# BMS_LOST_V2.net
KiCad netlist of a schematic drawn in Altium Designer
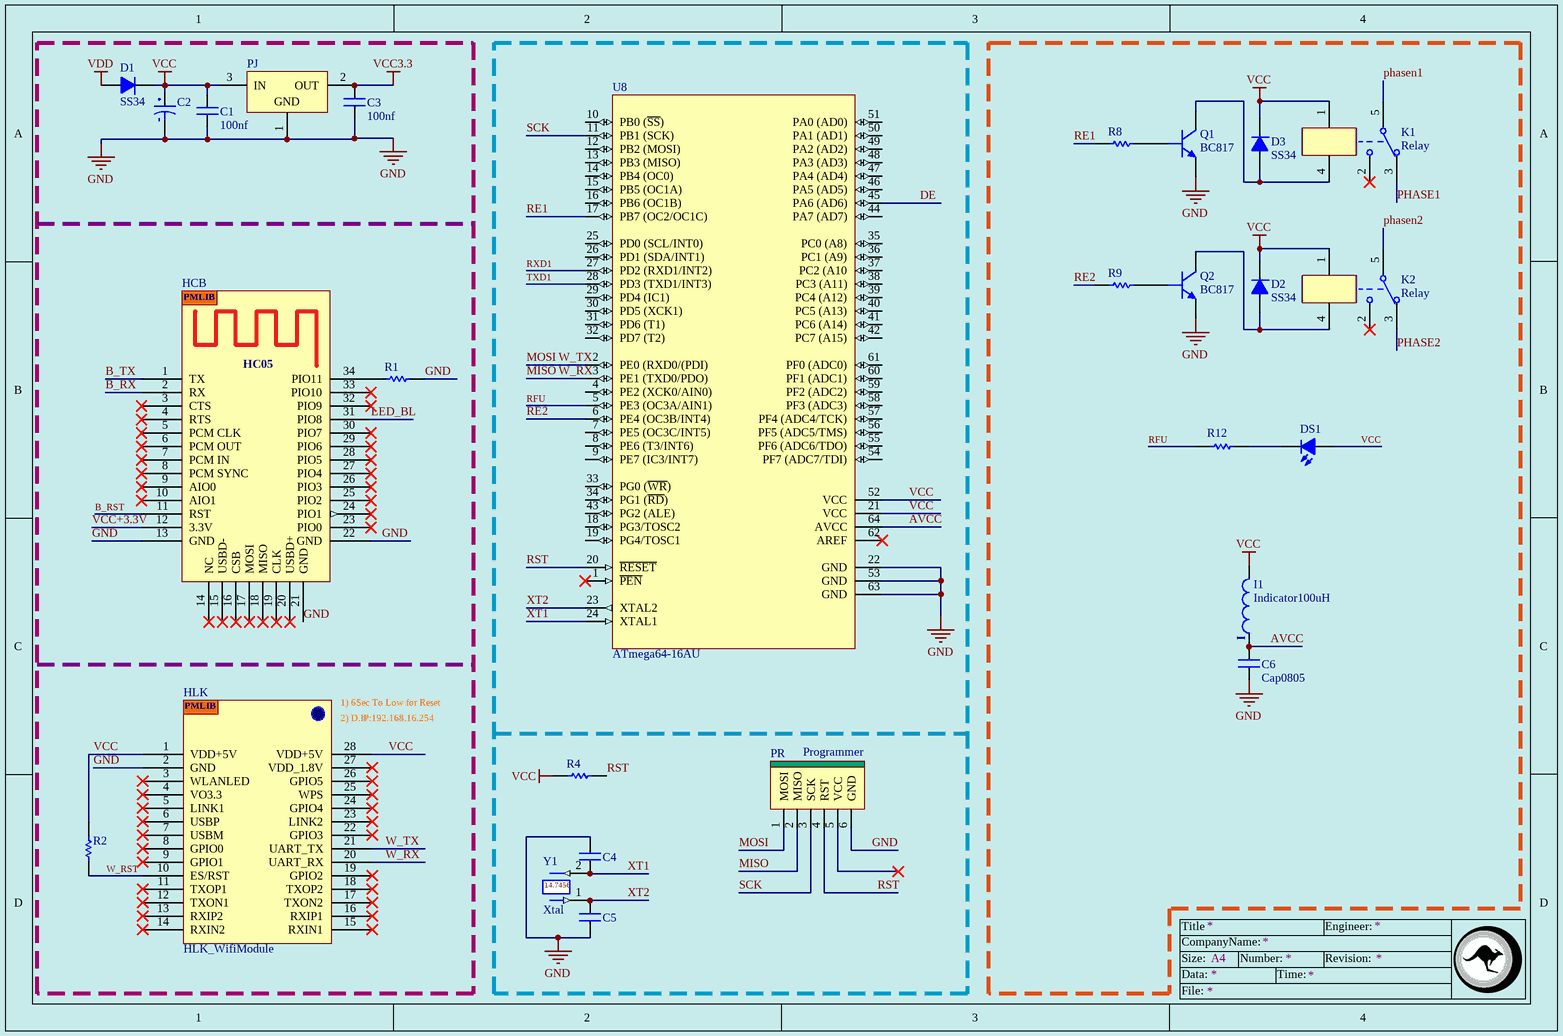
[diagram p0: BMS_LOST_V2.SchDoc]

(export (version "E")
  (design (tool "Eeschema 10.0.6"))
  (components
    (comp (ref "C1")
      (value "100nf")
      (footprint "Cap0805")
      (description "surface mount capacitor (size 805)")
      (libsource (lib "PMLIB") (part "Cap0805"))
    )
    (comp (ref "C2") (value "Cap_4mm") (footprint "2220") (libsource (lib "PMLIB") (part "Cap_Pola")))
    (comp (ref "C3")
      (value "100nf")
      (footprint "Cap0805")
      (description "surface mount capacitor (size 805)")
      (libsource (lib "PMLIB") (part "Cap0805"))
    )
    (comp (ref "C4")
      (value "CAP 805")
      (footprint "Cap0805")
      (description "surface mount capacitor (size 805)")
      (libsource (lib "PMLIB") (part "Cap0805"))
    )
    (comp (ref "C5")
      (value "CAP 805")
      (footprint "Cap0805")
      (description "surface mount capacitor (size 805)")
      (libsource (lib "PMLIB") (part "Cap0805"))
    )
    (comp (ref "C6")
      (value "Cap0805")
      (footprint "Cap0805")
      (description "surface mount capacitor (size 805)")
      (libsource (lib "PMLIB") (part "Cap0805"))
    )
    (comp (ref "D1") (value "SS34") (footprint "Diod-1A-SMD") (libsource (lib "PMLIB") (part "Diode")))
    (comp (ref "D2") (value "SS34") (footprint "Diod-1A-SMD") (libsource (lib "PMLIB") (part "Diode")))
    (comp (ref "D3") (value "SS34") (footprint "Diod-1A-SMD") (libsource (lib "PMLIB") (part "Diode")))
    (comp (ref "DS1") (value "LED1") (footprint "LED3MM") (libsource (lib "PMLIB") (part "LED1")))
    (comp (ref "HC")
      (value "HC05_Bluetooth")
      (footprint "HC05_Bluetooth")
      (libsource (lib "PMLIB") (part "HC05_Bluetooth"))
    )
    (comp (ref "HLK")
      (value "HLK_WifiModule")
      (footprint "HLK")
      (libsource (lib "PMLIB") (part "HLK_WifiModule"))
    )
    (comp (ref "I1")
      (value "Indicator100uH")
      (footprint "Indicator0805")
      (libsource (lib "PMLIB") (part "Indicator100uH"))
    )
    (comp (ref "K1")
      (value "Relay")
      (footprint "RelayMilionMiniS-Z")
      (libsource (lib "PMLIB") (part "RelayMilon"))
    )
    (comp (ref "K2")
      (value "Relay")
      (footprint "RelayMilionMiniS-Z")
      (libsource (lib "PMLIB") (part "RelayMilon"))
    )
    (comp (ref "PJ")
      (value "PJ1117_3.3V")
      (footprint "PJ1117s")
      (libsource (lib "PMLIB") (part "PJ1117_3.3V"))
    )
    (comp (ref "PR")
      (value "Programmer")
      (footprint "Programmer")
      (libsource (lib "PMLIB") (part "Programmer"))
    )
    (comp (ref "Q1") (value "BC817") (footprint "SOT23") (libsource (lib "PMLIB") (part "Transistor NPN")))
    (comp (ref "Q2") (value "BC817") (footprint "SOT23") (libsource (lib "PMLIB") (part "Transistor NPN")))
    (comp (ref "R1") (value "Res 0805") (footprint "R0805") (libsource (lib "PMLIB") (part "Res 0805")))
    (comp (ref "R2") (value "Res 0805") (footprint "R0805") (libsource (lib "PMLIB") (part "Res 0805")))
    (comp (ref "R4") (value "Res 0805") (footprint "R0805") (libsource (lib "PMLIB") (part "Res 0805")))
    (comp (ref "R8") (value "Res 0805") (footprint "R0805") (libsource (lib "PMLIB") (part "Res 0805")))
    (comp (ref "R9") (value "Res 0805") (footprint "R0805") (libsource (lib "PMLIB") (part "Res 0805")))
    (comp (ref "R12") (value "330") (footprint "R0805") (libsource (lib "PMLIB") (part "Res 0805")))
    (comp (ref "U8")
      (value "ATmega64-16AU")
      (footprint "64A_L")
      (libsource (lib "Atmel Microcontroller megaAVR") (part "ATmega64-16AU"))
    )
    (comp (ref "Y1") (value "Xtal") (footprint "CrystallB") (libsource (lib "PMLIB") (part "Crystal")))
  )
  (nets
    (net (code "1") (name "/AVCC") (class "Default")
      (node (ref "C6") (pin "2") (pinfunction "2_2") (pintype "passive"))
      (node (ref "I1") (pin "1") (pinfunction "1_1") (pintype "passive"))
      (node (ref "U8") (pin "64") (pinfunction "AVCC_64") (pintype "power_in"))
    )
    (net (code "2") (name "/B_RST") (class "Default")
      (node (ref "HC") (pin "11") (pinfunction "RST_11") (pintype "passive"))
    )
    (net (code "3") (name "/B_RX") (class "Default")
      (node (ref "HC") (pin "2") (pinfunction "RX_2") (pintype "passive"))
    )
    (net (code "4") (name "/B_TX") (class "Default")
      (node (ref "HC") (pin "1") (pinfunction "TX_1") (pintype "passive"))
    )
    (net (code "5") (name "/DE") (class "Default")
      (node (ref "U8") (pin "45") (pinfunction "PA6_(AD6)_45") (pintype "bidirectional"))
    )
    (net (code "6") (name "/LED_BL") (class "Default")
      (node (ref "HC") (pin "31") (pinfunction "PIO8_31") (pintype "passive"))
    )
    (net (code "7") (name "/MISO") (class "Default")
      (node (ref "HLK") (pin "20") (pinfunction "UART_RX_20") (pintype "passive"))
      (node (ref "PR") (pin "2") (pinfunction "MISO_2") (pintype "passive"))
      (node (ref "U8") (pin "3") (pinfunction "PE1_(TXD0/PDO)_3") (pintype "bidirectional"))
    )
    (net (code "8") (name "/MOSI") (class "Default")
      (node (ref "HLK") (pin "21") (pinfunction "UART_TX_21") (pintype "passive"))
      (node (ref "PR") (pin "1") (pinfunction "MOSI_1") (pintype "passive"))
      (node (ref "U8") (pin "2") (pinfunction "PE0_(RXD0/(PDI)_2") (pintype "bidirectional"))
    )
    (net (code "9") (name "/PHASE1") (class "Default")
      (node (ref "K1") (pin "3") (pinfunction "3_3") (pintype "passive"))
    )
    (net (code "10") (name "/PHASE2") (class "Default")
      (node (ref "K2") (pin "3") (pinfunction "3_3") (pintype "passive"))
    )
    (net (code "11") (name "/RE1") (class "Default")
      (node (ref "R8") (pin "2") (pinfunction "2_2") (pintype "passive"))
      (node (ref "U8") (pin "17") (pinfunction "PB7_(OC2/OC1C)_17") (pintype "bidirectional"))
    )
    (net (code "12") (name "/RE2") (class "Default")
      (node (ref "R9") (pin "2") (pinfunction "2_2") (pintype "passive"))
      (node (ref "U8") (pin "6") (pinfunction "PE4_(OC3B/INT4)_6") (pintype "bidirectional"))
    )
    (net (code "13") (name "/RFU") (class "Default")
      (node (ref "R12") (pin "2") (pinfunction "2_2") (pintype "passive"))
      (node (ref "U8") (pin "5") (pinfunction "PE3_(OC3A/AIN1)_5") (pintype "bidirectional"))
    )
    (net (code "14") (name "/RST") (class "Default")
      (node (ref "PR") (pin "4") (pinfunction "RST_4") (pintype "passive"))
      (node (ref "R4") (pin "1") (pinfunction "1_1") (pintype "passive"))
      (node (ref "U8") (pin "20") (pinfunction "~{RESET}_20") (pintype "input"))
    )
    (net (code "15") (name "/RXD1") (class "Default")
      (node (ref "U8") (pin "27") (pinfunction "PD2_(RXD1/INT2)_27") (pintype "bidirectional"))
    )
    (net (code "16") (name "/SCK") (class "Default")
      (node (ref "PR") (pin "3") (pinfunction "SCK_3") (pintype "passive"))
      (node (ref "U8") (pin "11") (pinfunction "PB1_(SCK)_11") (pintype "bidirectional"))
    )
    (net (code "17") (name "/TXD1") (class "Default")
      (node (ref "U8") (pin "28") (pinfunction "PD3_(TXD1/INT3)_28") (pintype "bidirectional"))
    )
    (net (code "18") (name "/VCC+3.3V") (class "Default")
      (node (ref "HC") (pin "12") (pinfunction "3.3V_12") (pintype "passive"))
    )
    (net (code "19") (name "/W_RST") (class "Default")
      (node (ref "HLK") (pin "10") (pinfunction "ES/RST_10") (pintype "passive"))
      (node (ref "R2") (pin "2") (pinfunction "2_2") (pintype "passive"))
    )
    (net (code "20") (name "/XT1") (class "Default")
      (node (ref "C4") (pin "1") (pinfunction "1_1") (pintype "passive"))
      (node (ref "U8") (pin "24") (pinfunction "XTAL1_24") (pintype "input"))
      (node (ref "Y1") (pin "2") (pinfunction "2_2") (pintype "input"))
    )
    (net (code "21") (name "/XT2") (class "Default")
      (node (ref "C5") (pin "1") (pinfunction "1_1") (pintype "passive"))
      (node (ref "U8") (pin "23") (pinfunction "XTAL2_23") (pintype "output"))
      (node (ref "Y1") (pin "1") (pinfunction "1_1") (pintype "output"))
    )
    (net (code "22") (name "/phasen1") (class "Default")
      (node (ref "K1") (pin "5") (pinfunction "5_5") (pintype "passive"))
    )
    (net (code "23") (name "/phasen2") (class "Default")
      (node (ref "K2") (pin "5") (pinfunction "5_5") (pintype "passive"))
    )
    (net (code "24") (name "GND") (class "Default")
      (node (ref "C1") (pin "2") (pinfunction "2_2") (pintype "passive"))
      (node (ref "C2") (pin "1") (pinfunction "1_1") (pintype "passive"))
      (node (ref "C3") (pin "2") (pinfunction "2_2") (pintype "passive"))
      (node (ref "C4") (pin "2") (pinfunction "2_2") (pintype "passive"))
      (node (ref "C5") (pin "2") (pinfunction "2_2") (pintype "passive"))
      (node (ref "C6") (pin "1") (pinfunction "1_1") (pintype "passive"))
      (node (ref "HC") (pin "13") (pinfunction "GND_13") (pintype "power_in"))
      (node (ref "HC") (pin "21") (pinfunction "GND_21") (pintype "passive"))
      (node (ref "HC") (pin "22") (pinfunction "GND_22") (pintype "passive"))
      (node (ref "HLK") (pin "2") (pinfunction "GND_2") (pintype "passive"))
      (node (ref "PJ") (pin "1") (pinfunction "GND_1") (pintype "power_in"))
      (node (ref "PR") (pin "6") (pinfunction "GND_6") (pintype "passive"))
      (node (ref "Q1") (pin "2") (pinfunction "E_2") (pintype "passive"))
      (node (ref "Q2") (pin "2") (pinfunction "E_2") (pintype "passive"))
      (node (ref "R1") (pin "1") (pinfunction "1_1") (pintype "passive"))
      (node (ref "U8") (pin "22") (pinfunction "GND_22") (pintype "power_in"))
      (node (ref "U8") (pin "53") (pinfunction "GND_53") (pintype "power_in"))
      (node (ref "U8") (pin "63") (pinfunction "GND_63") (pintype "power_in"))
    )
    (net (code "25") (name "Net-(DS1-PadK)") (class "Default")
      (node (ref "DS1") (pin "K") (pinfunction "K_K") (pintype "passive"))
      (node (ref "R12") (pin "1") (pinfunction "1_1") (pintype "passive"))
    )
    (net (code "26") (name "Net-(HCB-PIO11)") (class "Default")
      (node (ref "HC") (pin "34") (pinfunction "PIO11_34") (pintype "passive"))
      (node (ref "R1") (pin "2") (pinfunction "2_2") (pintype "passive"))
    )
    (net (code "27") (name "Net-(Q1-B)") (class "Default")
      (node (ref "Q1") (pin "1") (pinfunction "B_1") (pintype "passive"))
      (node (ref "R8") (pin "1") (pinfunction "1_1") (pintype "passive"))
    )
    (net (code "28") (name "Net-(Q1-C)") (class "Default")
      (node (ref "D3") (pin "A") (pinfunction "A_A") (pintype "passive"))
      (node (ref "K1") (pin "4") (pinfunction "4_4") (pintype "passive"))
      (node (ref "Q1") (pin "3") (pinfunction "C_3") (pintype "passive"))
    )
    (net (code "29") (name "Net-(Q2-B)") (class "Default")
      (node (ref "Q2") (pin "1") (pinfunction "B_1") (pintype "passive"))
      (node (ref "R9") (pin "1") (pinfunction "1_1") (pintype "passive"))
    )
    (net (code "30") (name "Net-(Q2-C)") (class "Default")
      (node (ref "D2") (pin "A") (pinfunction "A_A") (pintype "passive"))
      (node (ref "K2") (pin "4") (pinfunction "4_4") (pintype "passive"))
      (node (ref "Q2") (pin "3") (pinfunction "C_3") (pintype "passive"))
    )
    (net (code "31") (name "VCC") (class "Default")
      (node (ref "C1") (pin "1") (pinfunction "1_1") (pintype "passive"))
      (node (ref "C2") (pin "2") (pinfunction "2_2") (pintype "passive"))
      (node (ref "D1") (pin "K") (pinfunction "K_K") (pintype "passive"))
      (node (ref "D2") (pin "K") (pinfunction "K_K") (pintype "passive"))
      (node (ref "D3") (pin "K") (pinfunction "K_K") (pintype "passive"))
      (node (ref "DS1") (pin "A") (pinfunction "A_A") (pintype "passive"))
      (node (ref "HLK") (pin "1") (pinfunction "VDD+5V_1") (pintype "passive"))
      (node (ref "HLK") (pin "28") (pinfunction "VDD+5V_28") (pintype "passive"))
      (node (ref "I1") (pin "2") (pinfunction "2_2") (pintype "passive"))
      (node (ref "K1") (pin "1") (pinfunction "1_1") (pintype "passive"))
      (node (ref "K2") (pin "1") (pinfunction "1_1") (pintype "passive"))
      (node (ref "PJ") (pin "3") (pinfunction "IN_3") (pintype "power_in"))
      (node (ref "R2") (pin "1") (pinfunction "1_1") (pintype "passive"))
      (node (ref "R4") (pin "2") (pinfunction "2_2") (pintype "passive"))
      (node (ref "U8") (pin "21") (pinfunction "VCC_21") (pintype "power_in"))
      (node (ref "U8") (pin "52") (pinfunction "VCC_52") (pintype "power_in"))
    )
    (net (code "32") (name "VCC3.3") (class "Default")
      (node (ref "C3") (pin "1") (pinfunction "1_1") (pintype "passive"))
      (node (ref "PJ") (pin "2") (pinfunction "OUT_2") (pintype "power_in"))
    )
    (net (code "33") (name "VDD") (class "Default")
      (node (ref "D1") (pin "A") (pinfunction "A_A") (pintype "passive"))
    )
    (net (code "34") (name "unconnected-(HCB-AIO0-Pad9)") (class "Default")
      (node (ref "HC") (pin "9") (pinfunction "AIO0_9") (pintype "passive+no_connect"))
    )
    (net (code "35") (name "unconnected-(HCB-AIO1-Pad10)") (class "Default")
      (node (ref "HC") (pin "10") (pinfunction "AIO1_10") (pintype "passive+no_connect"))
    )
    (net (code "36") (name "unconnected-(HCB-CLK-Pad19)") (class "Default")
      (node (ref "HC") (pin "19") (pinfunction "CLK_19") (pintype "passive+no_connect"))
    )
    (net (code "37") (name "unconnected-(HCB-CSB-Pad16)") (class "Default")
      (node (ref "HC") (pin "16") (pinfunction "CSB_16") (pintype "passive+no_connect"))
    )
    (net (code "38") (name "unconnected-(HCB-CTS-Pad3)") (class "Default")
      (node (ref "HC") (pin "3") (pinfunction "CTS_3") (pintype "passive+no_connect"))
    )
    (net (code "39") (name "unconnected-(HCB-MISO-Pad18)") (class "Default")
      (node (ref "HC") (pin "18") (pinfunction "MISO_18") (pintype "passive+no_connect"))
    )
    (net (code "40") (name "unconnected-(HCB-MOSI-Pad17)") (class "Default")
      (node (ref "HC") (pin "17") (pinfunction "MOSI_17") (pintype "passive+no_connect"))
    )
    (net (code "41") (name "unconnected-(HCB-NC-Pad14)") (class "Default")
      (node (ref "HC") (pin "14") (pinfunction "NC_14") (pintype "passive+no_connect"))
    )
    (net (code "42") (name "unconnected-(HCB-PCM_CLK-Pad5)") (class "Default")
      (node (ref "HC") (pin "5") (pinfunction "PCM_CLK_5") (pintype "passive+no_connect"))
    )
    (net (code "43") (name "unconnected-(HCB-PCM_IN-Pad7)") (class "Default")
      (node (ref "HC") (pin "7") (pinfunction "PCM_IN_7") (pintype "passive+no_connect"))
    )
    (net (code "44") (name "unconnected-(HCB-PCM_OUT-Pad6)") (class "Default")
      (node (ref "HC") (pin "6") (pinfunction "PCM_OUT_6") (pintype "passive+no_connect"))
    )
    (net (code "45") (name "unconnected-(HCB-PCM_SYNC-Pad8)") (class "Default")
      (node (ref "HC") (pin "8") (pinfunction "PCM_SYNC_8") (pintype "passive+no_connect"))
    )
    (net (code "46") (name "unconnected-(HCB-PIO0-Pad23)") (class "Default")
      (node (ref "HC") (pin "23") (pinfunction "PIO0_23") (pintype "passive+no_connect"))
    )
    (net (code "47") (name "unconnected-(HCB-PIO1-Pad24)") (class "Default")
      (node (ref "HC") (pin "24") (pinfunction "PIO1_24") (pintype "output+no_connect"))
    )
    (net (code "48") (name "unconnected-(HCB-PIO2-Pad25)") (class "Default")
      (node (ref "HC") (pin "25") (pinfunction "PIO2_25") (pintype "passive+no_connect"))
    )
    (net (code "49") (name "unconnected-(HCB-PIO3-Pad26)") (class "Default")
      (node (ref "HC") (pin "26") (pinfunction "PIO3_26") (pintype "passive+no_connect"))
    )
    (net (code "50") (name "unconnected-(HCB-PIO4-Pad27)") (class "Default")
      (node (ref "HC") (pin "27") (pinfunction "PIO4_27") (pintype "passive+no_connect"))
    )
    (net (code "51") (name "unconnected-(HCB-PIO5-Pad28)") (class "Default")
      (node (ref "HC") (pin "28") (pinfunction "PIO5_28") (pintype "passive+no_connect"))
    )
    (net (code "52") (name "unconnected-(HCB-PIO6-Pad29)") (class "Default")
      (node (ref "HC") (pin "29") (pinfunction "PIO6_29") (pintype "passive+no_connect"))
    )
    (net (code "53") (name "unconnected-(HCB-PIO7-Pad30)") (class "Default")
      (node (ref "HC") (pin "30") (pinfunction "PIO7_30") (pintype "passive+no_connect"))
    )
    (net (code "54") (name "unconnected-(HCB-PIO9-Pad32)") (class "Default")
      (node (ref "HC") (pin "32") (pinfunction "PIO9_32") (pintype "passive+no_connect"))
    )
    (net (code "55") (name "unconnected-(HCB-PIO10-Pad33)") (class "Default")
      (node (ref "HC") (pin "33") (pinfunction "PIO10_33") (pintype "passive+no_connect"))
    )
    (net (code "56") (name "unconnected-(HCB-RTS-Pad4)") (class "Default")
      (node (ref "HC") (pin "4") (pinfunction "RTS_4") (pintype "passive+no_connect"))
    )
    (net (code "57") (name "unconnected-(HCB-USBD+-Pad20)") (class "Default")
      (node (ref "HC") (pin "20") (pinfunction "USBD+_20") (pintype "passive+no_connect"))
    )
    (net (code "58") (name "unconnected-(HCB-USBD--Pad15)") (class "Default")
      (node (ref "HC") (pin "15") (pinfunction "USBD-_15") (pintype "passive+no_connect"))
    )
    (net (code "59") (name "unconnected-(HLK-GPIO0-Pad8)") (class "Default")
      (node (ref "HLK") (pin "8") (pinfunction "GPIO0_8") (pintype "passive+no_connect"))
    )
    (net (code "60") (name "unconnected-(HLK-GPIO1-Pad9)") (class "Default")
      (node (ref "HLK") (pin "9") (pinfunction "GPIO1_9") (pintype "passive+no_connect"))
    )
    (net (code "61") (name "unconnected-(HLK-GPIO2-Pad19)") (class "Default")
      (node (ref "HLK") (pin "19") (pinfunction "GPIO2_19") (pintype "passive+no_connect"))
    )
    (net (code "62") (name "unconnected-(HLK-GPIO3-Pad22)") (class "Default")
      (node (ref "HLK") (pin "22") (pinfunction "GPIO3_22") (pintype "passive+no_connect"))
    )
    (net (code "63") (name "unconnected-(HLK-GPIO4-Pad24)") (class "Default")
      (node (ref "HLK") (pin "24") (pinfunction "GPIO4_24") (pintype "passive+no_connect"))
    )
    (net (code "64") (name "unconnected-(HLK-GPIO5-Pad26)") (class "Default")
      (node (ref "HLK") (pin "26") (pinfunction "GPIO5_26") (pintype "passive+no_connect"))
    )
    (net (code "65") (name "unconnected-(HLK-LINK1-Pad5)") (class "Default")
      (node (ref "HLK") (pin "5") (pinfunction "LINK1_5") (pintype "passive+no_connect"))
    )
    (net (code "66") (name "unconnected-(HLK-LINK2-Pad23)") (class "Default")
      (node (ref "HLK") (pin "23") (pinfunction "LINK2_23") (pintype "passive+no_connect"))
    )
    (net (code "67") (name "unconnected-(HLK-RXIN1-Pad15)") (class "Default")
      (node (ref "HLK") (pin "15") (pinfunction "RXIN1_15") (pintype "passive+no_connect"))
    )
    (net (code "68") (name "unconnected-(HLK-RXIN2-Pad14)") (class "Default")
      (node (ref "HLK") (pin "14") (pinfunction "RXIN2_14") (pintype "passive+no_connect"))
    )
    (net (code "69") (name "unconnected-(HLK-RXIP1-Pad16)") (class "Default")
      (node (ref "HLK") (pin "16") (pinfunction "RXIP1_16") (pintype "passive+no_connect"))
    )
    (net (code "70") (name "unconnected-(HLK-RXIP2-Pad13)") (class "Default")
      (node (ref "HLK") (pin "13") (pinfunction "RXIP2_13") (pintype "passive+no_connect"))
    )
    (net (code "71") (name "unconnected-(HLK-TXON1-Pad12)") (class "Default")
      (node (ref "HLK") (pin "12") (pinfunction "TXON1_12") (pintype "passive+no_connect"))
    )
    (net (code "72") (name "unconnected-(HLK-TXON2-Pad17)") (class "Default")
      (node (ref "HLK") (pin "17") (pinfunction "TXON2_17") (pintype "passive+no_connect"))
    )
    (net (code "73") (name "unconnected-(HLK-TXOP1-Pad11)") (class "Default")
      (node (ref "HLK") (pin "11") (pinfunction "TXOP1_11") (pintype "passive+no_connect"))
    )
    (net (code "74") (name "unconnected-(HLK-TXOP2-Pad18)") (class "Default")
      (node (ref "HLK") (pin "18") (pinfunction "TXOP2_18") (pintype "passive+no_connect"))
    )
    (net (code "75") (name "unconnected-(HLK-USBM-Pad7)") (class "Default")
      (node (ref "HLK") (pin "7") (pinfunction "USBM_7") (pintype "passive+no_connect"))
    )
    (net (code "76") (name "unconnected-(HLK-USBP-Pad6)") (class "Default")
      (node (ref "HLK") (pin "6") (pinfunction "USBP_6") (pintype "passive+no_connect"))
    )
    (net (code "77") (name "unconnected-(HLK-VDD_1.8V-Pad27)") (class "Default")
      (node (ref "HLK") (pin "27") (pinfunction "VDD_1.8V_27") (pintype "passive+no_connect"))
    )
    (net (code "78") (name "unconnected-(HLK-VO3.3-Pad4)") (class "Default")
      (node (ref "HLK") (pin "4") (pinfunction "VO3.3_4") (pintype "passive+no_connect"))
    )
    (net (code "79") (name "unconnected-(HLK-WLANLED-Pad3)") (class "Default")
      (node (ref "HLK") (pin "3") (pinfunction "WLANLED_3") (pintype "passive+no_connect"))
    )
    (net (code "80") (name "unconnected-(HLK-WPS-Pad25)") (class "Default")
      (node (ref "HLK") (pin "25") (pinfunction "WPS_25") (pintype "passive+no_connect"))
    )
    (net (code "81") (name "unconnected-(K1-Pad2)") (class "Default")
      (node (ref "K1") (pin "2") (pinfunction "2_2") (pintype "passive+no_connect"))
    )
    (net (code "82") (name "unconnected-(K2-Pad2)") (class "Default")
      (node (ref "K2") (pin "2") (pinfunction "2_2") (pintype "passive+no_connect"))
    )
    (net (code "83") (name "unconnected-(PR-VCC-Pad5)") (class "Default")
      (node (ref "PR") (pin "5") (pinfunction "VCC_5") (pintype "passive+no_connect"))
    )
    (net (code "84") (name "unconnected-(U8-AREF-Pad62)") (class "Default")
      (node (ref "U8") (pin "62") (pinfunction "AREF_62") (pintype "passive+no_connect"))
    )
    (net (code "85") (name "unconnected-(U8-PA0_(AD0)-Pad51)") (class "Default")
      (node (ref "U8") (pin "51") (pinfunction "PA0_(AD0)_51") (pintype "bidirectional"))
    )
    (net (code "86") (name "unconnected-(U8-PA1_(AD1)-Pad50)") (class "Default")
      (node (ref "U8") (pin "50") (pinfunction "PA1_(AD1)_50") (pintype "bidirectional"))
    )
    (net (code "87") (name "unconnected-(U8-PA2_(AD2)-Pad49)") (class "Default")
      (node (ref "U8") (pin "49") (pinfunction "PA2_(AD2)_49") (pintype "bidirectional"))
    )
    (net (code "88") (name "unconnected-(U8-PA3_(AD3)-Pad48)") (class "Default")
      (node (ref "U8") (pin "48") (pinfunction "PA3_(AD3)_48") (pintype "bidirectional"))
    )
    (net (code "89") (name "unconnected-(U8-PA4_(AD4)-Pad47)") (class "Default")
      (node (ref "U8") (pin "47") (pinfunction "PA4_(AD4)_47") (pintype "bidirectional"))
    )
    (net (code "90") (name "unconnected-(U8-PA5_(AD5)-Pad46)") (class "Default")
      (node (ref "U8") (pin "46") (pinfunction "PA5_(AD5)_46") (pintype "bidirectional"))
    )
    (net (code "91") (name "unconnected-(U8-PA7_(AD7)-Pad44)") (class "Default")
      (node (ref "U8") (pin "44") (pinfunction "PA7_(AD7)_44") (pintype "bidirectional"))
    )
    (net (code "92") (name "unconnected-(U8-PB0_(~{SS})-Pad10)") (class "Default")
      (node (ref "U8") (pin "10") (pinfunction "PB0_(~{SS})_10") (pintype "bidirectional"))
    )
    (net (code "93") (name "unconnected-(U8-PB2_(MOSI)-Pad12)") (class "Default")
      (node (ref "U8") (pin "12") (pinfunction "PB2_(MOSI)_12") (pintype "bidirectional"))
    )
    (net (code "94") (name "unconnected-(U8-PB3_(MISO)-Pad13)") (class "Default")
      (node (ref "U8") (pin "13") (pinfunction "PB3_(MISO)_13") (pintype "bidirectional"))
    )
    (net (code "95") (name "unconnected-(U8-PB4_(OC0)-Pad14)") (class "Default")
      (node (ref "U8") (pin "14") (pinfunction "PB4_(OC0)_14") (pintype "bidirectional"))
    )
    (net (code "96") (name "unconnected-(U8-PB5_(OC1A)-Pad15)") (class "Default")
      (node (ref "U8") (pin "15") (pinfunction "PB5_(OC1A)_15") (pintype "bidirectional"))
    )
    (net (code "97") (name "unconnected-(U8-PB6_(OC1B)-Pad16)") (class "Default")
      (node (ref "U8") (pin "16") (pinfunction "PB6_(OC1B)_16") (pintype "bidirectional"))
    )
    (net (code "98") (name "unconnected-(U8-PC0_(A8)-Pad35)") (class "Default")
      (node (ref "U8") (pin "35") (pinfunction "PC0_(A8)_35") (pintype "bidirectional"))
    )
    (net (code "99") (name "unconnected-(U8-PC1_(A9)-Pad36)") (class "Default")
      (node (ref "U8") (pin "36") (pinfunction "PC1_(A9)_36") (pintype "bidirectional"))
    )
    (net (code "100") (name "unconnected-(U8-PC2_(A10-Pad37)") (class "Default")
      (node (ref "U8") (pin "37") (pinfunction "PC2_(A10_37") (pintype "bidirectional"))
    )
    (net (code "101") (name "unconnected-(U8-PC3_(A11)-Pad38)") (class "Default")
      (node (ref "U8") (pin "38") (pinfunction "PC3_(A11)_38") (pintype "bidirectional"))
    )
    (net (code "102") (name "unconnected-(U8-PC4_(A12)-Pad39)") (class "Default")
      (node (ref "U8") (pin "39") (pinfunction "PC4_(A12)_39") (pintype "bidirectional"))
    )
    (net (code "103") (name "unconnected-(U8-PC5_(A13)-Pad40)") (class "Default")
      (node (ref "U8") (pin "40") (pinfunction "PC5_(A13)_40") (pintype "bidirectional"))
    )
    (net (code "104") (name "unconnected-(U8-PC6_(A14)-Pad41)") (class "Default")
      (node (ref "U8") (pin "41") (pinfunction "PC6_(A14)_41") (pintype "bidirectional"))
    )
    (net (code "105") (name "unconnected-(U8-PC7_(A15)-Pad42)") (class "Default")
      (node (ref "U8") (pin "42") (pinfunction "PC7_(A15)_42") (pintype "bidirectional"))
    )
    (net (code "106") (name "unconnected-(U8-PD0_(SCL{slash}INT0)-Pad25)") (class "Default")
      (node (ref "U8") (pin "25") (pinfunction "PD0_(SCL/INT0)_25") (pintype "bidirectional"))
    )
    (net (code "107") (name "unconnected-(U8-PD1_(SDA{slash}INT1)-Pad26)") (class "Default")
      (node (ref "U8") (pin "26") (pinfunction "PD1_(SDA/INT1)_26") (pintype "bidirectional"))
    )
    (net (code "108") (name "unconnected-(U8-PD4_(IC1)-Pad29)") (class "Default")
      (node (ref "U8") (pin "29") (pinfunction "PD4_(IC1)_29") (pintype "bidirectional"))
    )
    (net (code "109") (name "unconnected-(U8-PD5_(XCK1)-Pad30)") (class "Default")
      (node (ref "U8") (pin "30") (pinfunction "PD5_(XCK1)_30") (pintype "bidirectional"))
    )
    (net (code "110") (name "unconnected-(U8-PD6_(T1)-Pad31)") (class "Default")
      (node (ref "U8") (pin "31") (pinfunction "PD6_(T1)_31") (pintype "bidirectional"))
    )
    (net (code "111") (name "unconnected-(U8-PD7_(T2)-Pad32)") (class "Default")
      (node (ref "U8") (pin "32") (pinfunction "PD7_(T2)_32") (pintype "bidirectional"))
    )
    (net (code "112") (name "unconnected-(U8-PE2_(XCK0{slash}AIN0)-Pad4)") (class "Default")
      (node (ref "U8") (pin "4") (pinfunction "PE2_(XCK0/AIN0)_4") (pintype "bidirectional"))
    )
    (net (code "113") (name "unconnected-(U8-PE5_(OC3C{slash}INT5)-Pad7)") (class "Default")
      (node (ref "U8") (pin "7") (pinfunction "PE5_(OC3C/INT5)_7") (pintype "bidirectional"))
    )
    (net (code "114") (name "unconnected-(U8-PE6_(T3{slash}INT6)-Pad8)") (class "Default")
      (node (ref "U8") (pin "8") (pinfunction "PE6_(T3/INT6)_8") (pintype "bidirectional"))
    )
    (net (code "115") (name "unconnected-(U8-PE7_(IC3{slash}INT7)-Pad9)") (class "Default")
      (node (ref "U8") (pin "9") (pinfunction "PE7_(IC3/INT7)_9") (pintype "bidirectional"))
    )
    (net (code "116") (name "unconnected-(U8-PF0_(ADC0)-Pad61)") (class "Default")
      (node (ref "U8") (pin "61") (pinfunction "PF0_(ADC0)_61") (pintype "bidirectional"))
    )
    (net (code "117") (name "unconnected-(U8-PF1_(ADC1)-Pad60)") (class "Default")
      (node (ref "U8") (pin "60") (pinfunction "PF1_(ADC1)_60") (pintype "bidirectional"))
    )
    (net (code "118") (name "unconnected-(U8-PF2_(ADC2)-Pad59)") (class "Default")
      (node (ref "U8") (pin "59") (pinfunction "PF2_(ADC2)_59") (pintype "bidirectional"))
    )
    (net (code "119") (name "unconnected-(U8-PF3_(ADC3)-Pad58)") (class "Default")
      (node (ref "U8") (pin "58") (pinfunction "PF3_(ADC3)_58") (pintype "bidirectional"))
    )
    (net (code "120") (name "unconnected-(U8-PF4_(ADC4{slash}TCK)-Pad57)") (class "Default")
      (node (ref "U8") (pin "57") (pinfunction "PF4_(ADC4/TCK)_57") (pintype "bidirectional"))
    )
    (net (code "121") (name "unconnected-(U8-PF5_(ADC5{slash}TMS)-Pad56)") (class "Default")
      (node (ref "U8") (pin "56") (pinfunction "PF5_(ADC5/TMS)_56") (pintype "bidirectional"))
    )
    (net (code "122") (name "unconnected-(U8-PF6_(ADC6{slash}TDO)-Pad55)") (class "Default")
      (node (ref "U8") (pin "55") (pinfunction "PF6_(ADC6/TDO)_55") (pintype "bidirectional"))
    )
    (net (code "123") (name "unconnected-(U8-PF7_(ADC7{slash}TDI)-Pad54)") (class "Default")
      (node (ref "U8") (pin "54") (pinfunction "PF7_(ADC7/TDI)_54") (pintype "bidirectional"))
    )
    (net (code "124") (name "unconnected-(U8-PG0_(~{WR})-Pad33)") (class "Default")
      (node (ref "U8") (pin "33") (pinfunction "PG0_(~{WR})_33") (pintype "bidirectional"))
    )
    (net (code "125") (name "unconnected-(U8-PG1_(~{RD})-Pad34)") (class "Default")
      (node (ref "U8") (pin "34") (pinfunction "PG1_(~{RD})_34") (pintype "bidirectional"))
    )
    (net (code "126") (name "unconnected-(U8-PG2_(ALE)-Pad43)") (class "Default")
      (node (ref "U8") (pin "43") (pinfunction "PG2_(ALE)_43") (pintype "bidirectional"))
    )
    (net (code "127") (name "unconnected-(U8-PG3{slash}TOSC2-Pad18)") (class "Default")
      (node (ref "U8") (pin "18") (pinfunction "PG3/TOSC2_18") (pintype "bidirectional"))
    )
    (net (code "128") (name "unconnected-(U8-PG4{slash}TOSC1-Pad19)") (class "Default")
      (node (ref "U8") (pin "19") (pinfunction "PG4/TOSC1_19") (pintype "bidirectional"))
    )
    (net (code "129") (name "unconnected-(U8-~{PEN}-Pad1)") (class "Default")
      (node (ref "U8") (pin "1") (pinfunction "~{PEN}_1") (pintype "input+no_connect"))
    )
  )
)
